# hepek-shield.net
KiCad netlist of a schematic drawn in EAGLE
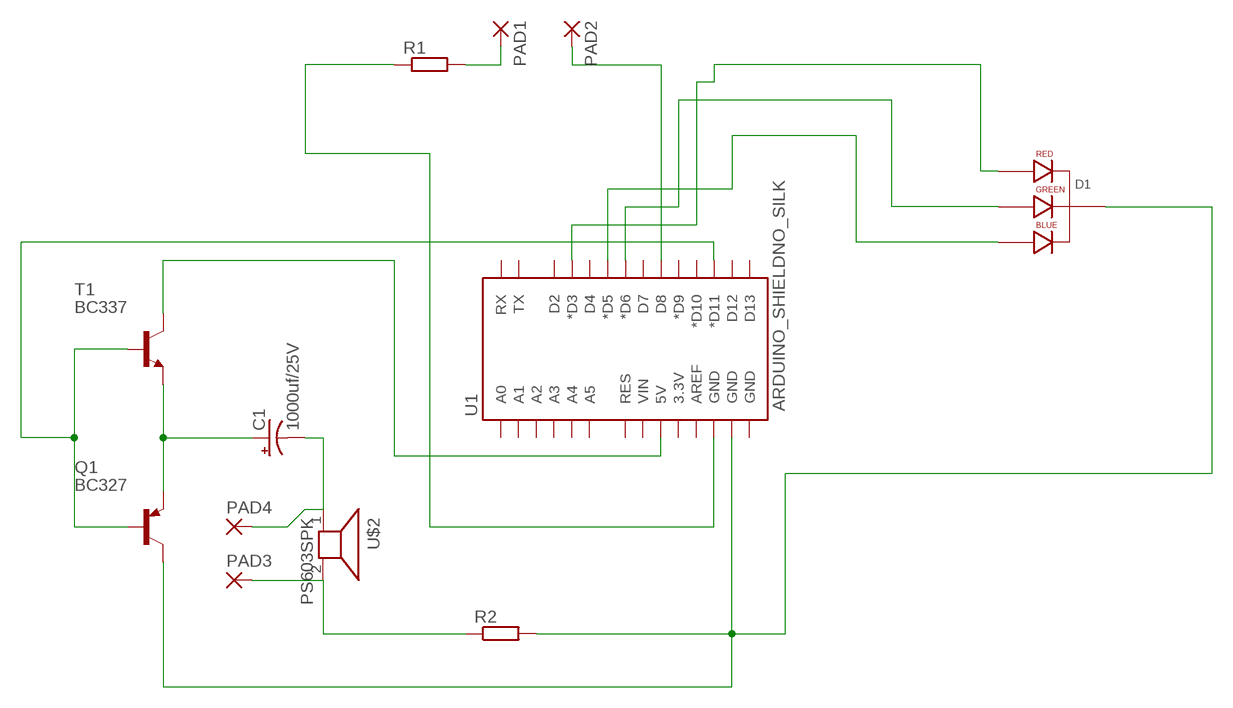
[diagram p0: schematic, sheet 1]

(export (version "E")
  (design (tool "Eeschema 10.0.6"))
  (components
    (comp (ref "C1")
      (value "1000uf/25V")
      (footprint "eagle-import:CPOL-RADIAL-1000UF-25V-KIT")
      (libsource (lib "eagle-import") (part "1000UF-25V(PTH)KIT"))
    )
    (comp (ref "D1")
      (value "LED-RGB-CC-THRUCLEAR")
      (footprint "eagle-import:LED-RGB-THRU")
      (libsource (lib "eagle-import") (part "LED-RGB-CC-THRUCLEAR"))
    )
    (comp (ref "PAD1")
      (value "2,15/1,0")
      (footprint "eagle-import:2,15_1,0")
      (libsource (lib "eagle-import") (part "2,15/1,0"))
    )
    (comp (ref "PAD2")
      (value "2,15/1,0")
      (footprint "eagle-import:2,15_1,0")
      (libsource (lib "eagle-import") (part "2,15/1,0"))
    )
    (comp (ref "PAD3")
      (value "2,15/1,0")
      (footprint "eagle-import:2,15_1,0")
      (libsource (lib "eagle-import") (part "2,15/1,0"))
    )
    (comp (ref "PAD4")
      (value "2,15/1,0")
      (footprint "eagle-import:2,15_1,0")
      (libsource (lib "eagle-import") (part "2,15/1,0"))
    )
    (comp (ref "Q1")
      (value "BC327")
      (footprint "eagle-import:TO92-EBC")
      (libsource (lib "eagle-import") (part "BC327"))
    )
    (comp (ref "R1")
      (value "R-EU_0204/7")
      (footprint "eagle-import:0204_7")
      (libsource (lib "eagle-import") (part "R-EU_0204/7"))
    )
    (comp (ref "R2")
      (value "R-EU_0204/7")
      (footprint "eagle-import:0204_7")
      (libsource (lib "eagle-import") (part "R-EU_0204/7"))
    )
    (comp (ref "T1")
      (value "BC337")
      (footprint "eagle-import:TO92")
      (libsource (lib "eagle-import") (part "BC337"))
    )
    (comp (ref "U$2")
      (value "PS603SPK")
      (footprint "eagle-import:PS603")
      (libsource (lib "eagle-import") (part "PS603SPK"))
    )
    (comp (ref "U1")
      (value "ARDUINO_SHIELDNO_SILK")
      (footprint "eagle-import:DUEMILANOVE_VIAS")
      (libsource (lib "eagle-import") (part "ARDUINO_SHIELDNO_SILK"))
    )
  )
  (nets
    (net (code "1") (name "Net-(D1-BLUE_CATHODE)") (class "Default")
      (node (ref "D1") (pin "4") (pinfunction "BLUE_CATHODE_4") (pintype "bidirectional"))
      (node (ref "U1") (pin "D5") (pinfunction "*D5_D5") (pintype "bidirectional"))
    )
    (net (code "2") (name "Net-(D1-CATHODE)") (class "Default")
      (node (ref "D1") (pin "2") (pinfunction "CATHODE_2") (pintype "bidirectional"))
      (node (ref "Q1") (pin "C") (pinfunction "C_C") (pintype "passive"))
      (node (ref "R2") (pin "2") (pinfunction "2_2") (pintype "passive"))
      (node (ref "U1") (pin "GND@1") (pinfunction "GND_GND@1") (pintype "bidirectional"))
    )
    (net (code "3") (name "Net-(D1-GREEN_CATHODE)") (class "Default")
      (node (ref "D1") (pin "3") (pinfunction "GREEN_CATHODE_3") (pintype "bidirectional"))
      (node (ref "U1") (pin "D6") (pinfunction "*D6_D6") (pintype "bidirectional"))
    )
    (net (code "4") (name "Net-(D1-RED_CATHODE)") (class "Default")
      (node (ref "D1") (pin "1") (pinfunction "RED_CATHODE_1") (pintype "bidirectional"))
      (node (ref "U1") (pin "D3") (pinfunction "*D3_D3") (pintype "bidirectional"))
    )
    (net (code "5") (name "Net-(PAD1-P)") (class "Default")
      (node (ref "PAD1") (pin "1") (pinfunction "P_1") (pintype "passive"))
      (node (ref "R1") (pin "2") (pinfunction "2_2") (pintype "passive"))
    )
    (net (code "6") (name "Net-(PAD2-P)") (class "Default")
      (node (ref "PAD2") (pin "1") (pinfunction "P_1") (pintype "passive"))
      (node (ref "U1") (pin "D8") (pinfunction "D8_D8") (pintype "bidirectional"))
    )
    (net (code "7") (name "Net-(PAD3-P)") (class "Default")
      (node (ref "PAD3") (pin "1") (pinfunction "P_1") (pintype "passive"))
      (node (ref "R2") (pin "1") (pinfunction "1_1") (pintype "passive"))
      (node (ref "U$2") (pin "2") (pinfunction "2_2") (pintype "passive"))
    )
    (net (code "8") (name "Net-(PAD4-P)") (class "Default")
      (node (ref "C1") (pin "-") (pinfunction "-_-") (pintype "passive"))
      (node (ref "PAD4") (pin "1") (pinfunction "P_1") (pintype "passive"))
      (node (ref "U$2") (pin "1") (pinfunction "1_1") (pintype "passive"))
    )
    (net (code "9") (name "Net-(R1-Pad1)") (class "Default")
      (node (ref "R1") (pin "1") (pinfunction "1_1") (pintype "passive"))
      (node (ref "U1") (pin "GND@2") (pinfunction "GND_GND@2") (pintype "bidirectional"))
    )
    (net (code "10") (name "Net-(T1-B)") (class "Default")
      (node (ref "Q1") (pin "B") (pinfunction "B_B") (pintype "passive"))
      (node (ref "T1") (pin "2") (pinfunction "B_2") (pintype "passive"))
      (node (ref "U1") (pin "D11") (pinfunction "*D11_D11") (pintype "bidirectional"))
    )
    (net (code "11") (name "Net-(T1-C)") (class "Default")
      (node (ref "T1") (pin "3") (pinfunction "C_3") (pintype "passive"))
      (node (ref "U1") (pin "5V") (pinfunction "5V_5V") (pintype "bidirectional"))
    )
    (net (code "12") (name "Net-(T1-E)") (class "Default")
      (node (ref "C1") (pin "+") (pinfunction "+_+") (pintype "passive"))
      (node (ref "Q1") (pin "E") (pinfunction "E_E") (pintype "passive"))
      (node (ref "T1") (pin "1") (pinfunction "E_1") (pintype "passive"))
    )
    (net (code "13") (name "unconnected-(U1-*D9-PadD9)") (class "Default")
      (node (ref "U1") (pin "D9") (pinfunction "*D9_D9") (pintype "bidirectional"))
    )
    (net (code "14") (name "unconnected-(U1-*D10-PadD10)") (class "Default")
      (node (ref "U1") (pin "D10") (pinfunction "*D10_D10") (pintype "bidirectional"))
    )
    (net (code "15") (name "unconnected-(U1-GND-PadGND@0)") (class "Default")
      (node (ref "U1") (pin "GND@0") (pinfunction "GND_GND@0") (pintype "bidirectional"))
    )
    (net (code "16") (name "unconnected-(U1-Pad3.3V)") (class "Default")
      (node (ref "U1") (pin "3.3V") (pinfunction "3.3V_3.3V") (pintype "bidirectional"))
    )
    (net (code "17") (name "unconnected-(U1-PadA0)") (class "Default")
      (node (ref "U1") (pin "A0") (pinfunction "A0_A0") (pintype "bidirectional"))
    )
    (net (code "18") (name "unconnected-(U1-PadA1)") (class "Default")
      (node (ref "U1") (pin "A1") (pinfunction "A1_A1") (pintype "bidirectional"))
    )
    (net (code "19") (name "unconnected-(U1-PadA2)") (class "Default")
      (node (ref "U1") (pin "A2") (pinfunction "A2_A2") (pintype "bidirectional"))
    )
    (net (code "20") (name "unconnected-(U1-PadA3)") (class "Default")
      (node (ref "U1") (pin "A3") (pinfunction "A3_A3") (pintype "bidirectional"))
    )
    (net (code "21") (name "unconnected-(U1-PadA4)") (class "Default")
      (node (ref "U1") (pin "A4") (pinfunction "A4_A4") (pintype "bidirectional"))
    )
    (net (code "22") (name "unconnected-(U1-PadA5)") (class "Default")
      (node (ref "U1") (pin "A5") (pinfunction "A5_A5") (pintype "bidirectional"))
    )
    (net (code "23") (name "unconnected-(U1-PadAREF)") (class "Default")
      (node (ref "U1") (pin "AREF") (pinfunction "AREF_AREF") (pintype "bidirectional"))
    )
    (net (code "24") (name "unconnected-(U1-PadD2)") (class "Default")
      (node (ref "U1") (pin "D2") (pinfunction "D2_D2") (pintype "bidirectional"))
    )
    (net (code "25") (name "unconnected-(U1-PadD4)") (class "Default")
      (node (ref "U1") (pin "D4") (pinfunction "D4_D4") (pintype "bidirectional"))
    )
    (net (code "26") (name "unconnected-(U1-PadD7)") (class "Default")
      (node (ref "U1") (pin "D7") (pinfunction "D7_D7") (pintype "bidirectional"))
    )
    (net (code "27") (name "unconnected-(U1-PadD12)") (class "Default")
      (node (ref "U1") (pin "D12") (pinfunction "D12_D12") (pintype "bidirectional"))
    )
    (net (code "28") (name "unconnected-(U1-PadD13)") (class "Default")
      (node (ref "U1") (pin "D13") (pinfunction "D13_D13") (pintype "bidirectional"))
    )
    (net (code "29") (name "unconnected-(U1-PadRES)") (class "Default")
      (node (ref "U1") (pin "RES") (pinfunction "RES_RES") (pintype "bidirectional"))
    )
    (net (code "30") (name "unconnected-(U1-PadRX)") (class "Default")
      (node (ref "U1") (pin "RX") (pinfunction "RX_RX") (pintype "bidirectional"))
    )
    (net (code "31") (name "unconnected-(U1-PadTX)") (class "Default")
      (node (ref "U1") (pin "TX") (pinfunction "TX_TX") (pintype "bidirectional"))
    )
    (net (code "32") (name "unconnected-(U1-PadVIN)") (class "Default")
      (node (ref "U1") (pin "VIN") (pinfunction "VIN_VIN") (pintype "bidirectional"))
    )
  )
)
